# 08_MT7688AN_DDR2.net
KiCad netlist of a schematic drawn in Altium Designer
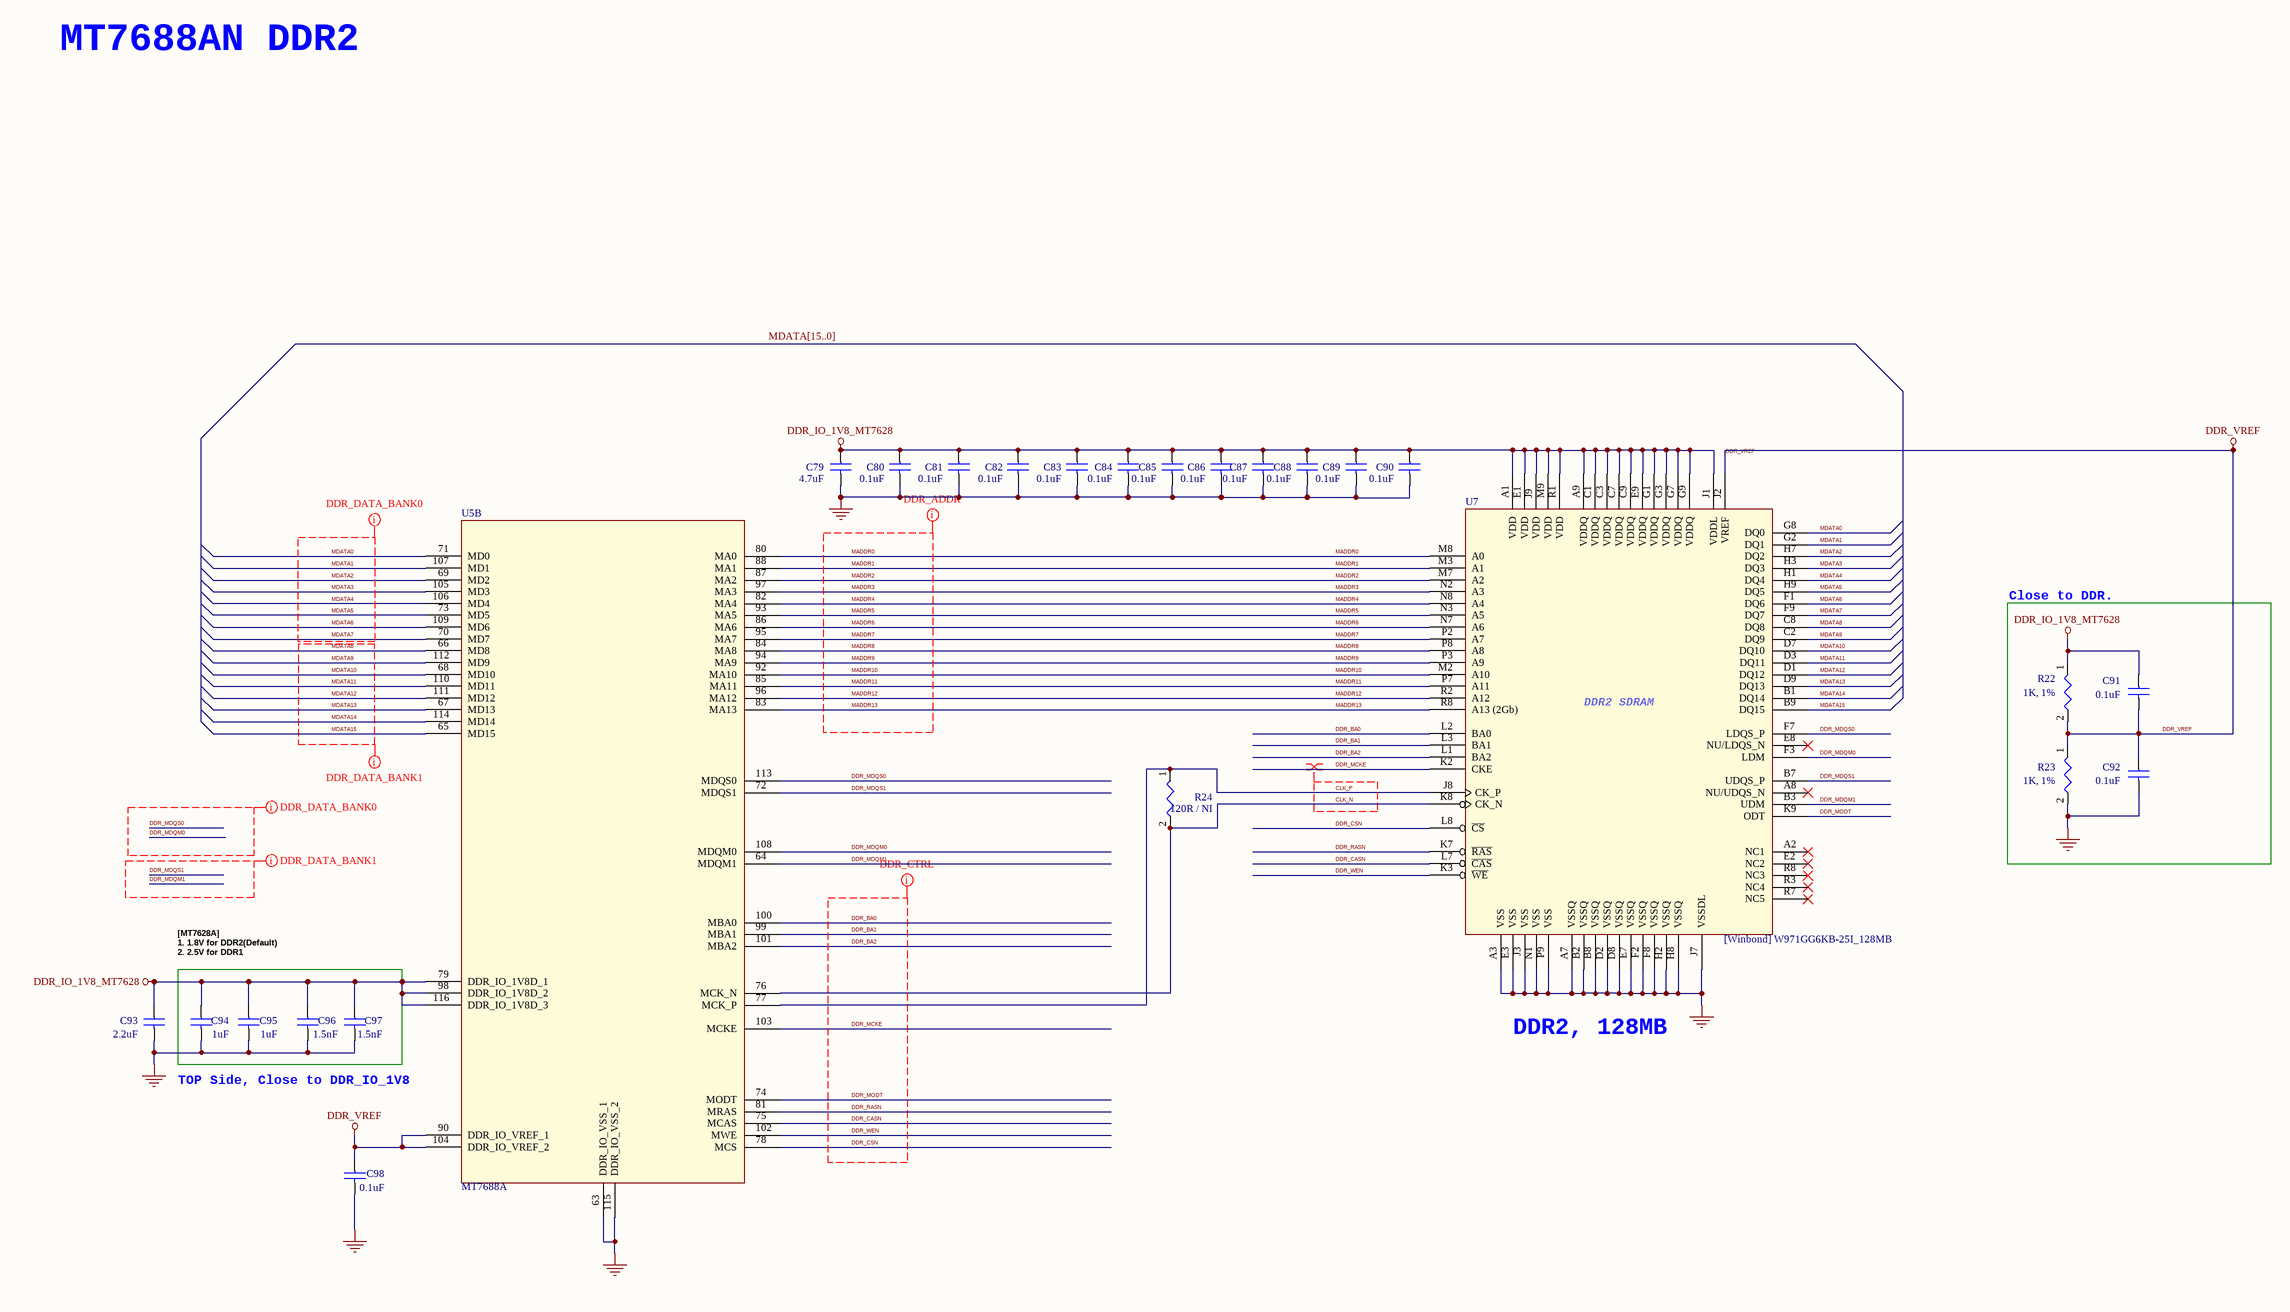
[diagram p0: 08. MT7688AN DDR2.SchDoc]

(export (version "E")
  (design (tool "Eeschema 10.0.6"))
  (components
    (comp (ref "C79")
      (value "4.7uF")
      (footprint "CAPC1608X90X35NL10T15")
      (libsource (lib "MT7688AN") (part "CAP NP"))
    )
    (comp (ref "C80")
      (value "0.1uF")
      (footprint "CAPC1005X60X30NL05T10")
      (libsource (lib "MT7688AN") (part "CAP NP"))
    )
    (comp (ref "C81")
      (value "0.1uF")
      (footprint "CAPC1005X60X30NL05T10")
      (libsource (lib "MT7688AN") (part "CAP NP"))
    )
    (comp (ref "C82")
      (value "0.1uF")
      (footprint "CAPC1005X60X30NL05T10")
      (libsource (lib "MT7688AN") (part "CAP NP"))
    )
    (comp (ref "C83")
      (value "0.1uF")
      (footprint "CAPC1005X60X30NL05T10")
      (libsource (lib "MT7688AN") (part "CAP NP"))
    )
    (comp (ref "C84")
      (value "0.1uF")
      (footprint "CAPC1005X60X30NL05T10")
      (libsource (lib "MT7688AN") (part "CAP NP"))
    )
    (comp (ref "C85")
      (value "0.1uF")
      (footprint "CAPC1005X60X30NL05T10")
      (libsource (lib "MT7688AN") (part "CAP NP"))
    )
    (comp (ref "C86")
      (value "0.1uF")
      (footprint "CAPC1005X60X30NL05T10")
      (libsource (lib "MT7688AN") (part "CAP NP"))
    )
    (comp (ref "C87")
      (value "0.1uF")
      (footprint "CAPC1005X60X30NL05T10")
      (libsource (lib "MT7688AN") (part "CAP NP"))
    )
    (comp (ref "C88")
      (value "0.1uF")
      (footprint "CAPC1005X60X30NL05T10")
      (libsource (lib "MT7688AN") (part "CAP NP"))
    )
    (comp (ref "C89")
      (value "0.1uF")
      (footprint "CAPC1005X60X30NL05T10")
      (libsource (lib "MT7688AN") (part "CAP NP"))
    )
    (comp (ref "C90")
      (value "0.1uF")
      (footprint "CAPC1005X60X30NL05T10")
      (libsource (lib "MT7688AN") (part "CAP NP"))
    )
    (comp (ref "C91")
      (value "0.1uF")
      (footprint "CAPC1005X60X30NL05T10")
      (libsource (lib "MT7688AN") (part "CAP NP"))
    )
    (comp (ref "C92")
      (value "0.1uF")
      (footprint "CAPC1005X60X30NL05T10")
      (libsource (lib "MT7688AN") (part "CAP NP"))
    )
    (comp (ref "C93")
      (value "2.2uF")
      (footprint "CAPC1608X90X35NL10T15")
      (libsource (lib "MT7688AN") (part "CAP NP"))
    )
    (comp (ref "C94")
      (value "1uF")
      (footprint "CAPC1608X90X35NL10T15")
      (libsource (lib "MT7688AN") (part "CAP NP"))
    )
    (comp (ref "C95")
      (value "1uF")
      (footprint "CAPC1608X90X35NL10T15")
      (libsource (lib "MT7688AN") (part "CAP NP"))
    )
    (comp (ref "C96")
      (value "1.5nF")
      (footprint "CAPC1005X60X30NL05T10")
      (libsource (lib "MT7688AN") (part "CAP NP"))
    )
    (comp (ref "C97")
      (value "1.5nF")
      (footprint "CAPC1005X60X30NL05T10")
      (libsource (lib "MT7688AN") (part "CAP NP"))
    )
    (comp (ref "C98")
      (value "0.1uF")
      (footprint "CAPC1005X60X30NL05T10")
      (libsource (lib "MT7688AN") (part "CAP NP"))
    )
    (comp (ref "R22")
      (value "1K, 1%")
      (footprint "RESC1005X35X25NL10T10")
      (libsource (lib "MT7688AN") (part "RES/0402_3"))
    )
    (comp (ref "R23")
      (value "1K, 1%")
      (footprint "RESC1005X35X25NL10T10")
      (libsource (lib "MT7688AN") (part "RES/0402_3"))
    )
    (comp (ref "R24")
      (value "120R / NI")
      (footprint "RLC 0201 M35")
      (libsource (lib "MT7688AN") (part "RES/0402_3"))
    )
    (comp (ref "U5")
      (value "MT7688A")
      (footprint "MT7628AN$2F$DRQFN156$2F$SMD$2F$P0.5$2F$12X12")
      (libsource (lib "MT7688AN") (part "MT7620N-n_26"))
    )
    (comp (ref "U7")
      (value "[Winbond] W971GG6KB-25I_128MB")
      (footprint "BGA84C80P9X15X12X8")
      (description "DDR2, 128MB")
      (libsource (lib "MT7688AN") (part "W971GG6KB-25I"))
    )
  )
  (nets
    (net (code "1") (name "/CLK_N") (class "Default")
      (node (ref "R24") (pin "2") (pinfunction "2_2") (pintype "passive"))
      (node (ref "U5") (pin "76") (pinfunction "MCK_N_76") (pintype "passive"))
      (node (ref "U7") (pin "K8") (pinfunction "CK_N_K8") (pintype "passive"))
    )
    (net (code "2") (name "/CLK_P") (class "Default")
      (node (ref "R24") (pin "1") (pinfunction "1_1") (pintype "passive"))
      (node (ref "U5") (pin "77") (pinfunction "MCK_P_77") (pintype "passive"))
      (node (ref "U7") (pin "J8") (pinfunction "CK_P_J8") (pintype "passive"))
    )
    (net (code "3") (name "/DDR_BA0") (class "Default")
      (node (ref "U5") (pin "100") (pinfunction "MBA0_100") (pintype "passive"))
      (node (ref "U7") (pin "L2") (pinfunction "BA0_L2") (pintype "passive"))
    )
    (net (code "4") (name "/DDR_BA1") (class "Default")
      (node (ref "U5") (pin "99") (pinfunction "MBA1_99") (pintype "passive"))
      (node (ref "U7") (pin "L3") (pinfunction "BA1_L3") (pintype "passive"))
    )
    (net (code "5") (name "/DDR_BA2") (class "Default")
      (node (ref "U5") (pin "101") (pinfunction "MBA2_101") (pintype "passive"))
      (node (ref "U7") (pin "L1") (pinfunction "BA2_L1") (pintype "passive"))
    )
    (net (code "6") (name "/DDR_CASN") (class "Default")
      (node (ref "U5") (pin "75") (pinfunction "MCAS_75") (pintype "passive"))
      (node (ref "U7") (pin "L7") (pinfunction "~{CAS}_L7") (pintype "passive"))
    )
    (net (code "7") (name "/DDR_CSN") (class "Default")
      (node (ref "U5") (pin "78") (pinfunction "MCS_78") (pintype "passive"))
      (node (ref "U7") (pin "L8") (pinfunction "~{CS}_L8") (pintype "passive"))
    )
    (net (code "8") (name "/DDR_MCKE") (class "Default")
      (node (ref "U5") (pin "103") (pinfunction "MCKE_103") (pintype "passive"))
      (node (ref "U7") (pin "K2") (pinfunction "CKE_K2") (pintype "passive"))
    )
    (net (code "9") (name "/DDR_MDQM0") (class "Default")
      (node (ref "U5") (pin "108") (pinfunction "MDQM0_108") (pintype "passive"))
      (node (ref "U7") (pin "F3") (pinfunction "LDM_F3") (pintype "passive"))
    )
    (net (code "10") (name "/DDR_MDQM1") (class "Default")
      (node (ref "U5") (pin "64") (pinfunction "MDQM1_64") (pintype "passive"))
      (node (ref "U7") (pin "B3") (pinfunction "UDM_B3") (pintype "passive"))
    )
    (net (code "11") (name "/DDR_MDQS0") (class "Default")
      (node (ref "U5") (pin "113") (pinfunction "MDQS0_113") (pintype "passive"))
      (node (ref "U7") (pin "F7") (pinfunction "LDQS_P_F7") (pintype "passive"))
    )
    (net (code "12") (name "/DDR_MDQS1") (class "Default")
      (node (ref "U5") (pin "72") (pinfunction "MDQS1_72") (pintype "passive"))
      (node (ref "U7") (pin "B7") (pinfunction "UDQS_P_B7") (pintype "passive"))
    )
    (net (code "13") (name "/DDR_MODT") (class "Default")
      (node (ref "U5") (pin "74") (pinfunction "MODT_74") (pintype "passive"))
      (node (ref "U7") (pin "K9") (pinfunction "ODT_K9") (pintype "passive"))
    )
    (net (code "14") (name "/DDR_RASN") (class "Default")
      (node (ref "U5") (pin "81") (pinfunction "MRAS_81") (pintype "passive"))
      (node (ref "U7") (pin "K7") (pinfunction "~{RAS}_K7") (pintype "passive"))
    )
    (net (code "15") (name "/DDR_WEN") (class "Default")
      (node (ref "U5") (pin "102") (pinfunction "MWE_102") (pintype "passive"))
      (node (ref "U7") (pin "K3") (pinfunction "~{WE}_K3") (pintype "passive"))
    )
    (net (code "16") (name "/MADDR0") (class "Default")
      (node (ref "U5") (pin "80") (pinfunction "MA0_80") (pintype "passive"))
      (node (ref "U7") (pin "M8") (pinfunction "A0_M8") (pintype "passive"))
    )
    (net (code "17") (name "/MADDR1") (class "Default")
      (node (ref "U5") (pin "88") (pinfunction "MA1_88") (pintype "passive"))
      (node (ref "U7") (pin "M3") (pinfunction "A1_M3") (pintype "passive"))
    )
    (net (code "18") (name "/MADDR2") (class "Default")
      (node (ref "U5") (pin "87") (pinfunction "MA2_87") (pintype "passive"))
      (node (ref "U7") (pin "M7") (pinfunction "A2_M7") (pintype "passive"))
    )
    (net (code "19") (name "/MADDR3") (class "Default")
      (node (ref "U5") (pin "97") (pinfunction "MA3_97") (pintype "passive"))
      (node (ref "U7") (pin "N2") (pinfunction "A3_N2") (pintype "passive"))
    )
    (net (code "20") (name "/MADDR4") (class "Default")
      (node (ref "U5") (pin "82") (pinfunction "MA4_82") (pintype "passive"))
      (node (ref "U7") (pin "N8") (pinfunction "A4_N8") (pintype "passive"))
    )
    (net (code "21") (name "/MADDR5") (class "Default")
      (node (ref "U5") (pin "93") (pinfunction "MA5_93") (pintype "passive"))
      (node (ref "U7") (pin "N3") (pinfunction "A5_N3") (pintype "passive"))
    )
    (net (code "22") (name "/MADDR6") (class "Default")
      (node (ref "U5") (pin "86") (pinfunction "MA6_86") (pintype "passive"))
      (node (ref "U7") (pin "N7") (pinfunction "A6_N7") (pintype "passive"))
    )
    (net (code "23") (name "/MADDR7") (class "Default")
      (node (ref "U5") (pin "95") (pinfunction "MA7_95") (pintype "passive"))
      (node (ref "U7") (pin "P2") (pinfunction "A7_P2") (pintype "passive"))
    )
    (net (code "24") (name "/MADDR8") (class "Default")
      (node (ref "U5") (pin "84") (pinfunction "MA8_84") (pintype "passive"))
      (node (ref "U7") (pin "P8") (pinfunction "A8_P8") (pintype "passive"))
    )
    (net (code "25") (name "/MADDR9") (class "Default")
      (node (ref "U5") (pin "94") (pinfunction "MA9_94") (pintype "passive"))
      (node (ref "U7") (pin "P3") (pinfunction "A9_P3") (pintype "passive"))
    )
    (net (code "26") (name "/MADDR10") (class "Default")
      (node (ref "U5") (pin "92") (pinfunction "MA10_92") (pintype "passive"))
      (node (ref "U7") (pin "M2") (pinfunction "A10_M2") (pintype "passive"))
    )
    (net (code "27") (name "/MADDR11") (class "Default")
      (node (ref "U5") (pin "85") (pinfunction "MA11_85") (pintype "passive"))
      (node (ref "U7") (pin "P7") (pinfunction "A11_P7") (pintype "passive"))
    )
    (net (code "28") (name "/MADDR12") (class "Default")
      (node (ref "U5") (pin "96") (pinfunction "MA12_96") (pintype "passive"))
      (node (ref "U7") (pin "R2") (pinfunction "A12_R2") (pintype "passive"))
    )
    (net (code "29") (name "/MADDR13") (class "Default")
      (node (ref "U5") (pin "83") (pinfunction "MA13_83") (pintype "passive"))
      (node (ref "U7") (pin "R8") (pinfunction "A13_(2Gb)_R8") (pintype "passive"))
    )
    (net (code "30") (name "/MDATA0") (class "Default")
      (node (ref "U5") (pin "71") (pinfunction "MD0_71") (pintype "passive"))
      (node (ref "U7") (pin "G8") (pinfunction "DQ0_G8") (pintype "passive"))
    )
    (net (code "31") (name "/MDATA1") (class "Default")
      (node (ref "U5") (pin "107") (pinfunction "MD1_107") (pintype "passive"))
      (node (ref "U7") (pin "G2") (pinfunction "DQ1_G2") (pintype "passive"))
    )
    (net (code "32") (name "/MDATA2") (class "Default")
      (node (ref "U5") (pin "69") (pinfunction "MD2_69") (pintype "passive"))
      (node (ref "U7") (pin "H7") (pinfunction "DQ2_H7") (pintype "passive"))
    )
    (net (code "33") (name "/MDATA3") (class "Default")
      (node (ref "U5") (pin "105") (pinfunction "MD3_105") (pintype "passive"))
      (node (ref "U7") (pin "H3") (pinfunction "DQ3_H3") (pintype "passive"))
    )
    (net (code "34") (name "/MDATA4") (class "Default")
      (node (ref "U5") (pin "106") (pinfunction "MD4_106") (pintype "passive"))
      (node (ref "U7") (pin "H1") (pinfunction "DQ4_H1") (pintype "passive"))
    )
    (net (code "35") (name "/MDATA5") (class "Default")
      (node (ref "U5") (pin "73") (pinfunction "MD5_73") (pintype "passive"))
      (node (ref "U7") (pin "H9") (pinfunction "DQ5_H9") (pintype "passive"))
    )
    (net (code "36") (name "/MDATA6") (class "Default")
      (node (ref "U5") (pin "109") (pinfunction "MD6_109") (pintype "passive"))
      (node (ref "U7") (pin "F1") (pinfunction "DQ6_F1") (pintype "passive"))
    )
    (net (code "37") (name "/MDATA7") (class "Default")
      (node (ref "U5") (pin "70") (pinfunction "MD7_70") (pintype "passive"))
      (node (ref "U7") (pin "F9") (pinfunction "DQ7_F9") (pintype "passive"))
    )
    (net (code "38") (name "/MDATA8") (class "Default")
      (node (ref "U5") (pin "66") (pinfunction "MD8_66") (pintype "passive"))
      (node (ref "U7") (pin "C8") (pinfunction "DQ8_C8") (pintype "passive"))
    )
    (net (code "39") (name "/MDATA9") (class "Default")
      (node (ref "U5") (pin "112") (pinfunction "MD9_112") (pintype "passive"))
      (node (ref "U7") (pin "C2") (pinfunction "DQ9_C2") (pintype "passive"))
    )
    (net (code "40") (name "/MDATA10") (class "Default")
      (node (ref "U5") (pin "68") (pinfunction "MD10_68") (pintype "passive"))
      (node (ref "U7") (pin "D7") (pinfunction "DQ10_D7") (pintype "passive"))
    )
    (net (code "41") (name "/MDATA11") (class "Default")
      (node (ref "U5") (pin "110") (pinfunction "MD11_110") (pintype "passive"))
      (node (ref "U7") (pin "D3") (pinfunction "DQ11_D3") (pintype "passive"))
    )
    (net (code "42") (name "/MDATA12") (class "Default")
      (node (ref "U5") (pin "111") (pinfunction "MD12_111") (pintype "passive"))
      (node (ref "U7") (pin "D1") (pinfunction "DQ12_D1") (pintype "passive"))
    )
    (net (code "43") (name "/MDATA13") (class "Default")
      (node (ref "U5") (pin "67") (pinfunction "MD13_67") (pintype "passive"))
      (node (ref "U7") (pin "D9") (pinfunction "DQ13_D9") (pintype "passive"))
    )
    (net (code "44") (name "/MDATA14") (class "Default")
      (node (ref "U5") (pin "114") (pinfunction "MD14_114") (pintype "passive"))
      (node (ref "U7") (pin "B1") (pinfunction "DQ14_B1") (pintype "passive"))
    )
    (net (code "45") (name "/MDATA15") (class "Default")
      (node (ref "U5") (pin "65") (pinfunction "MD15_65") (pintype "passive"))
      (node (ref "U7") (pin "B9") (pinfunction "DQ15_B9") (pintype "passive"))
    )
    (net (code "47") (name "DDR_IO_1V8_MT7628") (class "Default")
      (node (ref "C79") (pin "1") (pinfunction "1_1") (pintype "passive"))
      (node (ref "C80") (pin "1") (pinfunction "1_1") (pintype "passive"))
      (node (ref "C81") (pin "1") (pinfunction "1_1") (pintype "passive"))
      (node (ref "C82") (pin "1") (pinfunction "1_1") (pintype "passive"))
      (node (ref "C83") (pin "1") (pinfunction "1_1") (pintype "passive"))
      (node (ref "C84") (pin "1") (pinfunction "1_1") (pintype "passive"))
      (node (ref "C85") (pin "1") (pinfunction "1_1") (pintype "passive"))
      (node (ref "C86") (pin "1") (pinfunction "1_1") (pintype "passive"))
      (node (ref "C87") (pin "1") (pinfunction "1_1") (pintype "passive"))
      (node (ref "C88") (pin "1") (pinfunction "1_1") (pintype "passive"))
      (node (ref "C89") (pin "1") (pinfunction "1_1") (pintype "passive"))
      (node (ref "C90") (pin "1") (pinfunction "1_1") (pintype "passive"))
      (node (ref "C91") (pin "1") (pinfunction "1_1") (pintype "passive"))
      (node (ref "C93") (pin "1") (pinfunction "1_1") (pintype "passive"))
      (node (ref "C94") (pin "1") (pinfunction "1_1") (pintype "passive"))
      (node (ref "C95") (pin "1") (pinfunction "1_1") (pintype "passive"))
      (node (ref "C96") (pin "1") (pinfunction "1_1") (pintype "passive"))
      (node (ref "C97") (pin "1") (pinfunction "1_1") (pintype "passive"))
      (node (ref "R22") (pin "1") (pinfunction "1_1") (pintype "passive"))
      (node (ref "U5") (pin "116") (pinfunction "DDR_IO_1V8D_3_116") (pintype "power_in"))
      (node (ref "U5") (pin "79") (pinfunction "DDR_IO_1V8D_1_79") (pintype "power_in"))
      (node (ref "U5") (pin "98") (pinfunction "DDR_IO_1V8D_2_98") (pintype "power_in"))
      (node (ref "U7") (pin "A1") (pinfunction "VDD_A1") (pintype "power_in"))
      (node (ref "U7") (pin "A9") (pinfunction "VDDQ_A9") (pintype "power_in"))
      (node (ref "U7") (pin "C1") (pinfunction "VDDQ_C1") (pintype "power_in"))
      (node (ref "U7") (pin "C3") (pinfunction "VDDQ_C3") (pintype "power_in"))
      (node (ref "U7") (pin "C7") (pinfunction "VDDQ_C7") (pintype "power_in"))
      (node (ref "U7") (pin "C9") (pinfunction "VDDQ_C9") (pintype "power_in"))
      (node (ref "U7") (pin "E1") (pinfunction "VDD_E1") (pintype "power_in"))
      (node (ref "U7") (pin "E9") (pinfunction "VDDQ_E9") (pintype "power_in"))
      (node (ref "U7") (pin "G1") (pinfunction "VDDQ_G1") (pintype "power_in"))
      (node (ref "U7") (pin "G3") (pinfunction "VDDQ_G3") (pintype "power_in"))
      (node (ref "U7") (pin "G7") (pinfunction "VDDQ_G7") (pintype "power_in"))
      (node (ref "U7") (pin "G9") (pinfunction "VDDQ_G9") (pintype "power_in"))
      (node (ref "U7") (pin "J1") (pinfunction "VDDL_J1") (pintype "power_in"))
      (node (ref "U7") (pin "J9") (pinfunction "VDD_J9") (pintype "power_in"))
      (node (ref "U7") (pin "M9") (pinfunction "VDD_M9") (pintype "power_in"))
      (node (ref "U7") (pin "R1") (pinfunction "VDD_R1") (pintype "power_in"))
    )
    (net (code "48") (name "DDR_VREF") (class "Default")
      (node (ref "C91") (pin "2") (pinfunction "2_2") (pintype "passive"))
      (node (ref "C92") (pin "1") (pinfunction "1_1") (pintype "passive"))
      (node (ref "C98") (pin "1") (pinfunction "1_1") (pintype "passive"))
      (node (ref "R22") (pin "2") (pinfunction "2_2") (pintype "passive"))
      (node (ref "R23") (pin "1") (pinfunction "1_1") (pintype "passive"))
      (node (ref "U5") (pin "104") (pinfunction "DDR_IO_VREF_2_104") (pintype "power_in"))
      (node (ref "U5") (pin "90") (pinfunction "DDR_IO_VREF_1_90") (pintype "power_in"))
      (node (ref "U7") (pin "J2") (pinfunction "VREF_J2") (pintype "power_in"))
    )
    (net (code "49") (name "GND") (class "Default")
      (node (ref "C79") (pin "2") (pinfunction "2_2") (pintype "passive"))
      (node (ref "C80") (pin "2") (pinfunction "2_2") (pintype "passive"))
      (node (ref "C81") (pin "2") (pinfunction "2_2") (pintype "passive"))
      (node (ref "C82") (pin "2") (pinfunction "2_2") (pintype "passive"))
      (node (ref "C83") (pin "2") (pinfunction "2_2") (pintype "passive"))
      (node (ref "C84") (pin "2") (pinfunction "2_2") (pintype "passive"))
      (node (ref "C85") (pin "2") (pinfunction "2_2") (pintype "passive"))
      (node (ref "C86") (pin "2") (pinfunction "2_2") (pintype "passive"))
      (node (ref "C87") (pin "2") (pinfunction "2_2") (pintype "passive"))
      (node (ref "C88") (pin "2") (pinfunction "2_2") (pintype "passive"))
      (node (ref "C89") (pin "2") (pinfunction "2_2") (pintype "passive"))
      (node (ref "C90") (pin "2") (pinfunction "2_2") (pintype "passive"))
      (node (ref "C92") (pin "2") (pinfunction "2_2") (pintype "passive"))
      (node (ref "C93") (pin "2") (pinfunction "2_2") (pintype "passive"))
      (node (ref "C94") (pin "2") (pinfunction "2_2") (pintype "passive"))
      (node (ref "C95") (pin "2") (pinfunction "2_2") (pintype "passive"))
      (node (ref "C96") (pin "2") (pinfunction "2_2") (pintype "passive"))
      (node (ref "C97") (pin "2") (pinfunction "2_2") (pintype "passive"))
      (node (ref "C98") (pin "2") (pinfunction "2_2") (pintype "passive"))
      (node (ref "R23") (pin "2") (pinfunction "2_2") (pintype "passive"))
      (node (ref "U5") (pin "115") (pinfunction "DDR_IO_VSS_2_115") (pintype "passive"))
      (node (ref "U5") (pin "63") (pinfunction "DDR_IO_VSS_1_63") (pintype "power_in"))
      (node (ref "U7") (pin "A3") (pinfunction "VSS_A3") (pintype "power_in"))
      (node (ref "U7") (pin "A7") (pinfunction "VSSQ_A7") (pintype "power_in"))
      (node (ref "U7") (pin "B2") (pinfunction "VSSQ_B2") (pintype "power_in"))
      (node (ref "U7") (pin "B8") (pinfunction "VSSQ_B8") (pintype "power_in"))
      (node (ref "U7") (pin "D2") (pinfunction "VSSQ_D2") (pintype "power_in"))
      (node (ref "U7") (pin "D8") (pinfunction "VSSQ_D8") (pintype "power_in"))
      (node (ref "U7") (pin "E3") (pinfunction "VSS_E3") (pintype "power_in"))
      (node (ref "U7") (pin "E7") (pinfunction "VSSQ_E7") (pintype "power_in"))
      (node (ref "U7") (pin "F2") (pinfunction "VSSQ_F2") (pintype "power_in"))
      (node (ref "U7") (pin "F8") (pinfunction "VSSQ_F8") (pintype "power_in"))
      (node (ref "U7") (pin "H2") (pinfunction "VSSQ_H2") (pintype "power_in"))
      (node (ref "U7") (pin "H8") (pinfunction "VSSQ_H8") (pintype "power_in"))
      (node (ref "U7") (pin "J3") (pinfunction "VSS_J3") (pintype "power_in"))
      (node (ref "U7") (pin "J7") (pinfunction "VSSDL_J7") (pintype "power_in"))
      (node (ref "U7") (pin "N1") (pinfunction "VSS_N1") (pintype "power_in"))
      (node (ref "U7") (pin "P9") (pinfunction "VSS_P9") (pintype "power_in"))
    )
    (net (code "50") (name "unconnected-(U7-NC1-PadA2)") (class "Default")
      (node (ref "U7") (pin "A2") (pinfunction "NC1_A2") (pintype "passive+no_connect"))
    )
    (net (code "51") (name "unconnected-(U7-NC2-PadE2)") (class "Default")
      (node (ref "U7") (pin "E2") (pinfunction "NC2_E2") (pintype "passive+no_connect"))
    )
    (net (code "52") (name "unconnected-(U7-NC3-PadR8)") (class "Default")
      (node (ref "U7") (pin "R8") (pinfunction "NC3_R8") (pintype "passive+no_connect"))
    )
    (net (code "53") (name "unconnected-(U7-NC4-PadR3)") (class "Default")
      (node (ref "U7") (pin "R3") (pinfunction "NC4_R3") (pintype "passive+no_connect"))
    )
    (net (code "54") (name "unconnected-(U7-NC5-PadR7)") (class "Default")
      (node (ref "U7") (pin "R7") (pinfunction "NC5_R7") (pintype "passive+no_connect"))
    )
    (net (code "55") (name "unconnected-(U7-NU{slash}LDQS_N-PadE8)") (class "Default")
      (node (ref "U7") (pin "E8") (pinfunction "NU/LDQS_N_E8") (pintype "passive+no_connect"))
    )
    (net (code "56") (name "unconnected-(U7-NU{slash}UDQS_N-PadA8)") (class "Default")
      (node (ref "U7") (pin "A8") (pinfunction "NU/UDQS_N_A8") (pintype "passive+no_connect"))
    )
  )
)
